# relay-interface-for-vn5640.net
KiCad netlist of a schematic drawn in EAGLE
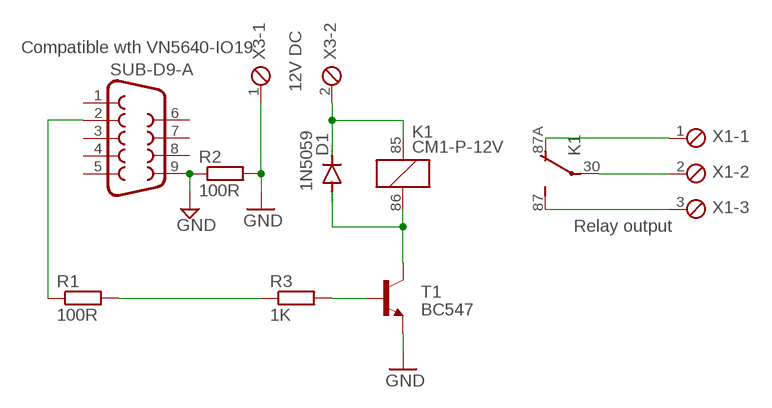
[diagram p0: schematic, sheet 1]

(export (version "E")
  (design (tool "Eeschema 10.0.6"))
  (components
    (comp (ref "D1")
      (value "1N5059")
      (footprint "eagle-import:DO204-10")
      (libsource (lib "eagle-import") (part "1N5059"))
    )
    (comp (ref "K1")
      (value "CM1-P-12V")
      (footprint "eagle-import:CM")
      (fields (field (name "MF") "AROMAT/ MATSUSHITA"))
      (libsource (lib "eagle-import") (part "CM1-P-12V"))
    )
    (comp (ref "R1")
      (value "100R")
      (footprint "eagle-import:0204V")
      (libsource (lib "eagle-import") (part "R-EU_0204/2V"))
    )
    (comp (ref "R2")
      (value "100R")
      (footprint "eagle-import:0204V")
      (libsource (lib "eagle-import") (part "R-EU_0204/2V"))
    )
    (comp (ref "R3")
      (value "1K")
      (footprint "eagle-import:0204V")
      (libsource (lib "eagle-import") (part "R-EU_0204/2V"))
    )
    (comp (ref "SUB-D9-A")
      (value "Compatible wth VN5640-IO19")
      (footprint "eagle-import:F09H")
      (libsource (lib "eagle-import") (part "F09H"))
    )
    (comp (ref "T1")
      (value "BC547")
      (footprint "eagle-import:TO92")
      (libsource (lib "eagle-import") (part "BC547"))
    )
    (comp (ref "X1")
      (value "Relay output")
      (footprint "eagle-import:3POL254")
      (libsource (lib "eagle-import") (part "MPT3"))
    )
    (comp (ref "X3")
      (value "12V DC")
      (footprint "eagle-import:2POL254")
      (libsource (lib "eagle-import") (part "MPT2"))
    )
  )
  (nets
    (net (code "1") (name "GND") (class "Default")
      (node (ref "R2") (pin "1") (pinfunction "1_1") (pintype "passive"))
      (node (ref "R2") (pin "2") (pinfunction "2_2") (pintype "passive"))
      (node (ref "SUB-D9-A") (pin "9") (pinfunction "9_9") (pintype "passive"))
      (node (ref "T1") (pin "1") (pinfunction "E_1") (pintype "passive"))
      (node (ref "X3") (pin "1") (pinfunction "1_1") (pintype "passive"))
    )
    (net (code "2") (name "Net-(K1A-1)") (class "Default")
      (node (ref "D1") (pin "C") (pinfunction "C_C") (pintype "passive"))
      (node (ref "K1") (pin "85") (pinfunction "1_85") (pintype "passive"))
      (node (ref "X3") (pin "2") (pinfunction "1_2") (pintype "passive"))
    )
    (net (code "3") (name "Net-(K1A-2)") (class "Default")
      (node (ref "D1") (pin "A") (pinfunction "A_A") (pintype "passive"))
      (node (ref "K1") (pin "86") (pinfunction "2_86") (pintype "passive"))
      (node (ref "T1") (pin "3") (pinfunction "C_3") (pintype "passive"))
    )
    (net (code "4") (name "Net-(K1B-O)") (class "Default")
      (node (ref "K1") (pin "87A") (pinfunction "O_87A") (pintype "passive"))
      (node (ref "X1") (pin "1") (pinfunction "1_1") (pintype "passive"))
    )
    (net (code "5") (name "Net-(K1B-P)") (class "Default")
      (node (ref "K1") (pin "30") (pinfunction "P_30") (pintype "passive"))
      (node (ref "X1") (pin "2") (pinfunction "1_2") (pintype "passive"))
    )
    (net (code "6") (name "Net-(K1B-S)") (class "Default")
      (node (ref "K1") (pin "87") (pinfunction "S_87") (pintype "passive"))
      (node (ref "X1") (pin "3") (pinfunction "1_3") (pintype "passive"))
    )
    (net (code "7") (name "Net-(R1-Pad1)") (class "Default")
      (node (ref "R1") (pin "1") (pinfunction "1_1") (pintype "passive"))
      (node (ref "SUB-D9-A") (pin "2") (pinfunction "2_2") (pintype "passive"))
    )
    (net (code "8") (name "Net-(R1-Pad2)") (class "Default")
      (node (ref "R1") (pin "2") (pinfunction "2_2") (pintype "passive"))
      (node (ref "R3") (pin "1") (pinfunction "1_1") (pintype "passive"))
    )
    (net (code "9") (name "Net-(T1-B)") (class "Default")
      (node (ref "R3") (pin "2") (pinfunction "2_2") (pintype "passive"))
      (node (ref "T1") (pin "2") (pinfunction "B_2") (pintype "passive"))
    )
    (net (code "10") (name "unconnected-(SUB-D9-A-Pad1)") (class "Default")
      (node (ref "SUB-D9-A") (pin "1") (pinfunction "1_1") (pintype "passive"))
    )
    (net (code "11") (name "unconnected-(SUB-D9-A-Pad3)") (class "Default")
      (node (ref "SUB-D9-A") (pin "3") (pinfunction "3_3") (pintype "passive"))
    )
    (net (code "12") (name "unconnected-(SUB-D9-A-Pad4)") (class "Default")
      (node (ref "SUB-D9-A") (pin "4") (pinfunction "4_4") (pintype "passive"))
    )
    (net (code "13") (name "unconnected-(SUB-D9-A-Pad5)") (class "Default")
      (node (ref "SUB-D9-A") (pin "5") (pinfunction "5_5") (pintype "passive"))
    )
    (net (code "14") (name "unconnected-(SUB-D9-A-Pad6)") (class "Default")
      (node (ref "SUB-D9-A") (pin "6") (pinfunction "6_6") (pintype "passive"))
    )
    (net (code "15") (name "unconnected-(SUB-D9-A-Pad7)") (class "Default")
      (node (ref "SUB-D9-A") (pin "7") (pinfunction "7_7") (pintype "passive"))
    )
    (net (code "16") (name "unconnected-(SUB-D9-A-Pad8)") (class "Default")
      (node (ref "SUB-D9-A") (pin "8") (pinfunction "8_8") (pintype "passive"))
    )
  )
)
